# 4_Protection.net
KiCad netlist of a schematic drawn in Altium Designer
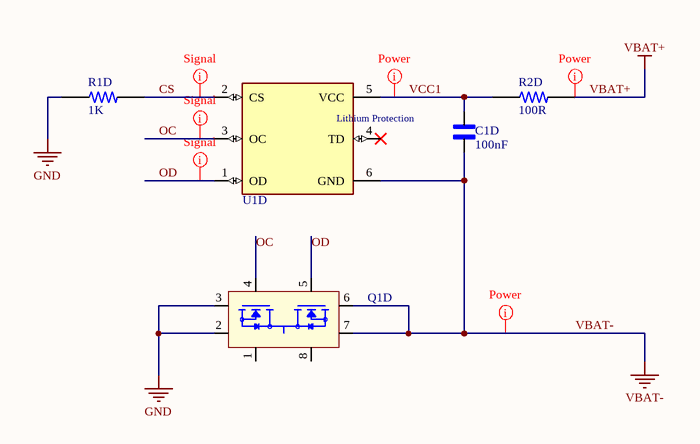
[diagram p0: 4_Protection.SchDoc]

(export (version "E")
  (design (tool "Eeschema 10.0.6"))
  (components
    (comp (ref "C1D")
      (value "100nF")
      (footprint "C-0603")
      (description "Ceramic Capacitor 16V 0603 (1608 Metric)")
      (fields (field (name "MP") "C0603C104J4RAC") (field (name "MF") "KEMET"))
      (libsource (lib "ESP-12F_WLED_IOT_LIPO") (part "C-0603"))
    )
    (comp (ref "Q1D")
      (value "!value")
      (footprint "FS8205A TSSOP-8")
      (description "Dual N-Channel Mosfet, Eq 8205A CEG8205A FS8205A STN8205A")
      (fields (field (name "MP") "FS8205A"))
      (libsource (lib "ESP-12F_WLED_IOT_LIPO") (part "FS8205A_2.0"))
    )
    (comp (ref "R1D")
      (value "1K")
      (footprint "R-0603")
      (description "0603")
      (fields (field (name "MP") "2-1623703-0") (field (name "TOLERANCE") "1%"))
      (libsource (lib "ESP-12F_WLED_IOT_LIPO") (part "R-0603"))
    )
    (comp (ref "R2D")
      (value "100R")
      (footprint "R-0603")
      (description "0603")
      (fields (field (name "MP") "2-1623703-0") (field (name "TOLERANCE") "1%"))
      (libsource (lib "ESP-12F_WLED_IOT_LIPO") (part "R-0603"))
    )
    (comp (ref "U1D")
      (value "DW01A")
      (footprint "SOT23-6")
      (description "Pushbutton Switch SPST-NC Standard Panel Mount, Front")
      (fields (field (name "MF") "Fortune Semiconductor"))
      (libsource (lib "ESP-12F_WLED_IOT_LIPO") (part "DW01A"))
    )
  )
  (nets
    (net (code "1") (name "/CS") (class "Default")
      (node (ref "R1D") (pin "2") (pinfunction "2_2") (pintype "passive"))
      (node (ref "U1D") (pin "2") (pinfunction "CS_2") (pintype "bidirectional"))
    )
    (net (code "2") (name "/OC") (class "Default")
      (node (ref "Q1D") (pin "4") (pinfunction "G1_4") (pintype "passive"))
      (node (ref "U1D") (pin "3") (pinfunction "OC_3") (pintype "bidirectional"))
    )
    (net (code "3") (name "/OD") (class "Default")
      (node (ref "Q1D") (pin "5") (pinfunction "G2_5") (pintype "passive"))
      (node (ref "U1D") (pin "1") (pinfunction "OD_1") (pintype "bidirectional"))
    )
    (net (code "4") (name "/VCC1") (class "Default")
      (node (ref "C1D") (pin "2") (pinfunction "2_2") (pintype "passive"))
      (node (ref "R2D") (pin "1") (pinfunction "1_1") (pintype "passive"))
      (node (ref "U1D") (pin "5") (pinfunction "VCC_5") (pintype "power_in"))
    )
    (net (code "5") (name "GND") (class "Default")
      (node (ref "Q1D") (pin "2") (pinfunction "S1_2") (pintype "passive"))
      (node (ref "Q1D") (pin "3") (pinfunction "S1_3") (pintype "passive"))
      (node (ref "R1D") (pin "1") (pinfunction "1_1") (pintype "passive"))
    )
    (net (code "6") (name "VBAT+") (class "Default")
      (node (ref "R2D") (pin "2") (pinfunction "2_2") (pintype "passive"))
    )
    (net (code "7") (name "VBAT-") (class "Default")
      (node (ref "C1D") (pin "1") (pinfunction "1_1") (pintype "passive"))
      (node (ref "Q1D") (pin "6") (pinfunction "S2_6") (pintype "passive"))
      (node (ref "Q1D") (pin "7") (pinfunction "S2_7") (pintype "passive"))
      (node (ref "U1D") (pin "6") (pinfunction "GND_6") (pintype "power_in"))
    )
    (net (code "8") (name "unconnected-(Q1D-D12-Pad1)") (class "Default")
      (node (ref "Q1D") (pin "1") (pinfunction "D12_1") (pintype "passive"))
    )
    (net (code "9") (name "unconnected-(Q1D-D12-Pad8)") (class "Default")
      (node (ref "Q1D") (pin "8") (pinfunction "D12_8") (pintype "passive"))
    )
    (net (code "10") (name "unconnected-(U1D-TD-Pad4)") (class "Default")
      (node (ref "U1D") (pin "4") (pinfunction "TD_4") (pintype "bidirectional+no_connect"))
    )
  )
)
